# 16_I2C_EEPROM_RTC.net
KiCad netlist of a schematic drawn in Altium Designer
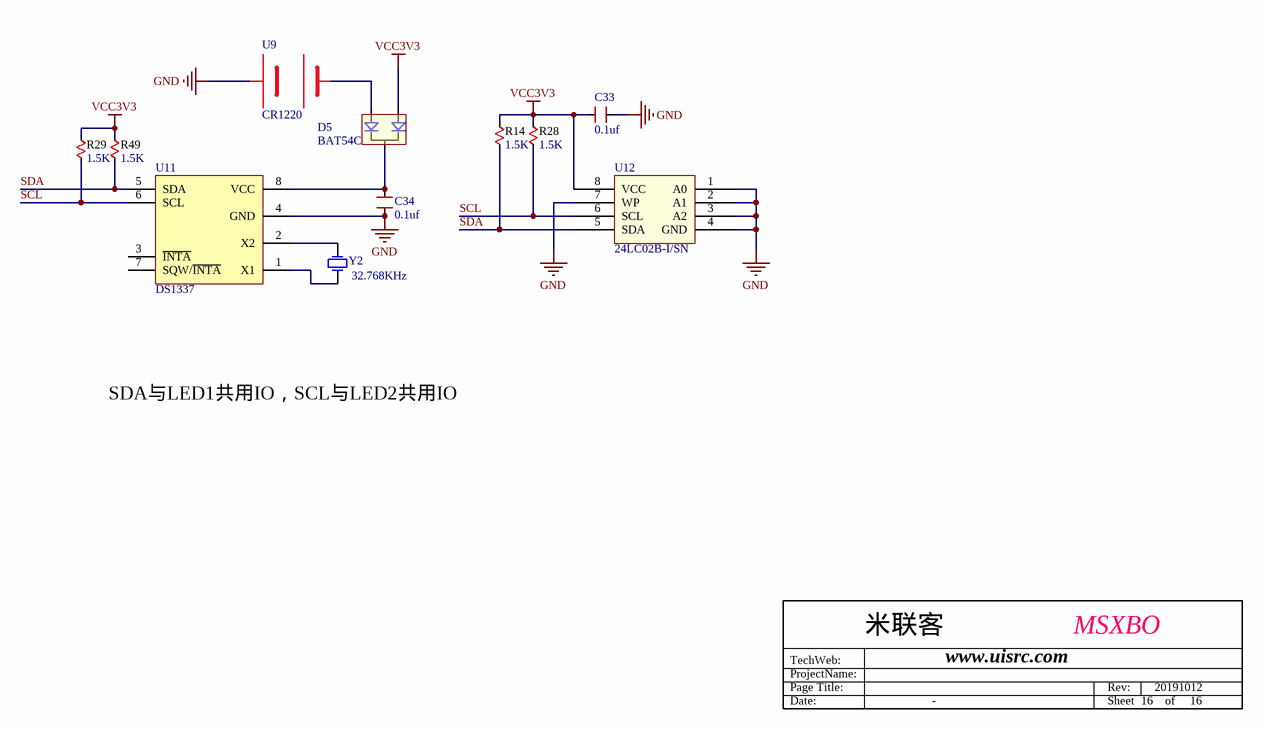
[diagram p0: 16_I2C_EEPROM_RTC.SchDoc]

(export (version "E")
  (design (tool "Eeschema 10.0.6"))
  (components
    (comp (ref "C33")
      (value "0.1uf")
      (footprint "CAP0402")
      (description "Generic Capacitor")
      (libsource (lib "Miz702fun_20160501") (part "CAPACITOR"))
    )
    (comp (ref "C34")
      (value "0.1uf")
      (footprint "CAP0402")
      (description "Generic Capacitor")
      (libsource (lib "Miz702fun_20160501") (part "CAPACITOR"))
    )
    (comp (ref "D5")
      (value "BAT54C")
      (footprint "SOT-23")
      (description "双肖特基二极管")
      (libsource (lib "PIONEER") (part "BAT54C"))
    )
    (comp (ref "R14")
      (value "1.5K")
      (footprint "RES0402")
      (description "Generic Resistor")
      (libsource (lib "MiSZ7020_core") (part "RESISTOR"))
    )
    (comp (ref "R28")
      (value "1.5K")
      (footprint "RES0402")
      (description "Generic Resistor")
      (libsource (lib "MiSZ7020_core") (part "RESISTOR"))
    )
    (comp (ref "R29")
      (value "1.5K")
      (footprint "RES0402")
      (description "Generic Resistor")
      (libsource (lib "MiSZ7020_core") (part "RESISTOR"))
    )
    (comp (ref "R49")
      (value "1.5K")
      (footprint "RES0402")
      (description "Generic Resistor")
      (libsource (lib "MiSZ7020_core") (part "RESISTOR"))
    )
    (comp (ref "U9") (value "CR1220") (footprint "R190") (libsource (lib "M7Z100F") (part "CR1220")))
    (comp (ref "U11") (value "DS1337") (footprint "SOP8") (libsource (lib "M7Z100F") (part "DS1337")))
    (comp (ref "U12")
      (value "24LC02B-I/SN")
      (footprint "SOP8")
      (libsource (lib "DVI-Schlib1") (part "24LC02B-I/SN"))
    )
    (comp (ref "Y2")
      (value "32.768KHz")
      (footprint "XTAL32")
      (description "普通晶振")
      (fields (field (name "PUBLISHER") "Altium Limited"))
      (libsource (lib "PIONEER") (part "XTAL"))
    )
  )
  (nets
    (net (code "1") (name "/SCL") (class "Default")
      (node (ref "R28") (pin "1") (pinfunction "1_1") (pintype "passive"))
      (node (ref "R29") (pin "1") (pinfunction "1_1") (pintype "passive"))
      (node (ref "U11") (pin "6") (pinfunction "SCL_6") (pintype "passive"))
      (node (ref "U12") (pin "6") (pinfunction "SCL_6") (pintype "passive"))
    )
    (net (code "2") (name "/SDA") (class "Default")
      (node (ref "R14") (pin "1") (pinfunction "1_1") (pintype "passive"))
      (node (ref "R49") (pin "1") (pinfunction "1_1") (pintype "passive"))
      (node (ref "U11") (pin "5") (pinfunction "SDA_5") (pintype "passive"))
      (node (ref "U12") (pin "5") (pinfunction "SDA_5") (pintype "passive"))
    )
    (net (code "3") (name "GND") (class "Default")
      (node (ref "C33") (pin "1") (pinfunction "1_1") (pintype "passive"))
      (node (ref "C34") (pin "2") (pinfunction "2_2") (pintype "passive"))
      (node (ref "U11") (pin "4") (pinfunction "GND_4") (pintype "passive"))
      (node (ref "U12") (pin "1") (pinfunction "A0_1") (pintype "passive"))
      (node (ref "U12") (pin "2") (pinfunction "A1_2") (pintype "passive"))
      (node (ref "U12") (pin "3") (pinfunction "A2_3") (pintype "passive"))
      (node (ref "U12") (pin "4") (pinfunction "GND_4") (pintype "passive"))
      (node (ref "U12") (pin "7") (pinfunction "WP_7") (pintype "passive"))
      (node (ref "U9") (pin "2") (pinfunction "2_2") (pintype "passive"))
    )
    (net (code "4") (name "Net-(D5-Pad2)") (class "Default")
      (node (ref "D5") (pin "2") (pintype "passive"))
      (node (ref "U9") (pin "1") (pinfunction "1_1") (pintype "passive"))
    )
    (net (code "5") (name "Net-(U11-VCC)") (class "Default")
      (node (ref "C34") (pin "1") (pinfunction "1_1") (pintype "passive"))
      (node (ref "D5") (pin "3") (pintype "passive"))
      (node (ref "U11") (pin "8") (pinfunction "VCC_8") (pintype "passive"))
    )
    (net (code "6") (name "Net-(U11-X1)") (class "Default")
      (node (ref "U11") (pin "1") (pinfunction "X1_1") (pintype "passive"))
      (node (ref "Y2") (pin "2") (pinfunction "OSC2_2") (pintype "passive"))
    )
    (net (code "7") (name "Net-(U11-X2)") (class "Default")
      (node (ref "U11") (pin "2") (pinfunction "X2_2") (pintype "passive"))
      (node (ref "Y2") (pin "1") (pinfunction "OSC1_1") (pintype "passive"))
    )
    (net (code "8") (name "VCC3V3") (class "Default")
      (node (ref "C33") (pin "2") (pinfunction "2_2") (pintype "passive"))
      (node (ref "D5") (pin "1") (pintype "passive"))
      (node (ref "R14") (pin "2") (pinfunction "2_2") (pintype "passive"))
      (node (ref "R28") (pin "2") (pinfunction "2_2") (pintype "passive"))
      (node (ref "R29") (pin "2") (pinfunction "2_2") (pintype "passive"))
      (node (ref "R49") (pin "2") (pinfunction "2_2") (pintype "passive"))
      (node (ref "U12") (pin "8") (pinfunction "VCC_8") (pintype "passive"))
    )
    (net (code "9") (name "unconnected-(U11-SQW{slash}~{INTA}-Pad7)") (class "Default")
      (node (ref "U11") (pin "7") (pinfunction "SQW/~{INTA}_7") (pintype "passive"))
    )
    (net (code "10") (name "unconnected-(U11-~{INTA}-Pad3)") (class "Default")
      (node (ref "U11") (pin "3") (pinfunction "~{INTA}_3") (pintype "passive"))
    )
  )
)
